# Power.net
KiCad netlist of a schematic drawn in Altium Designer
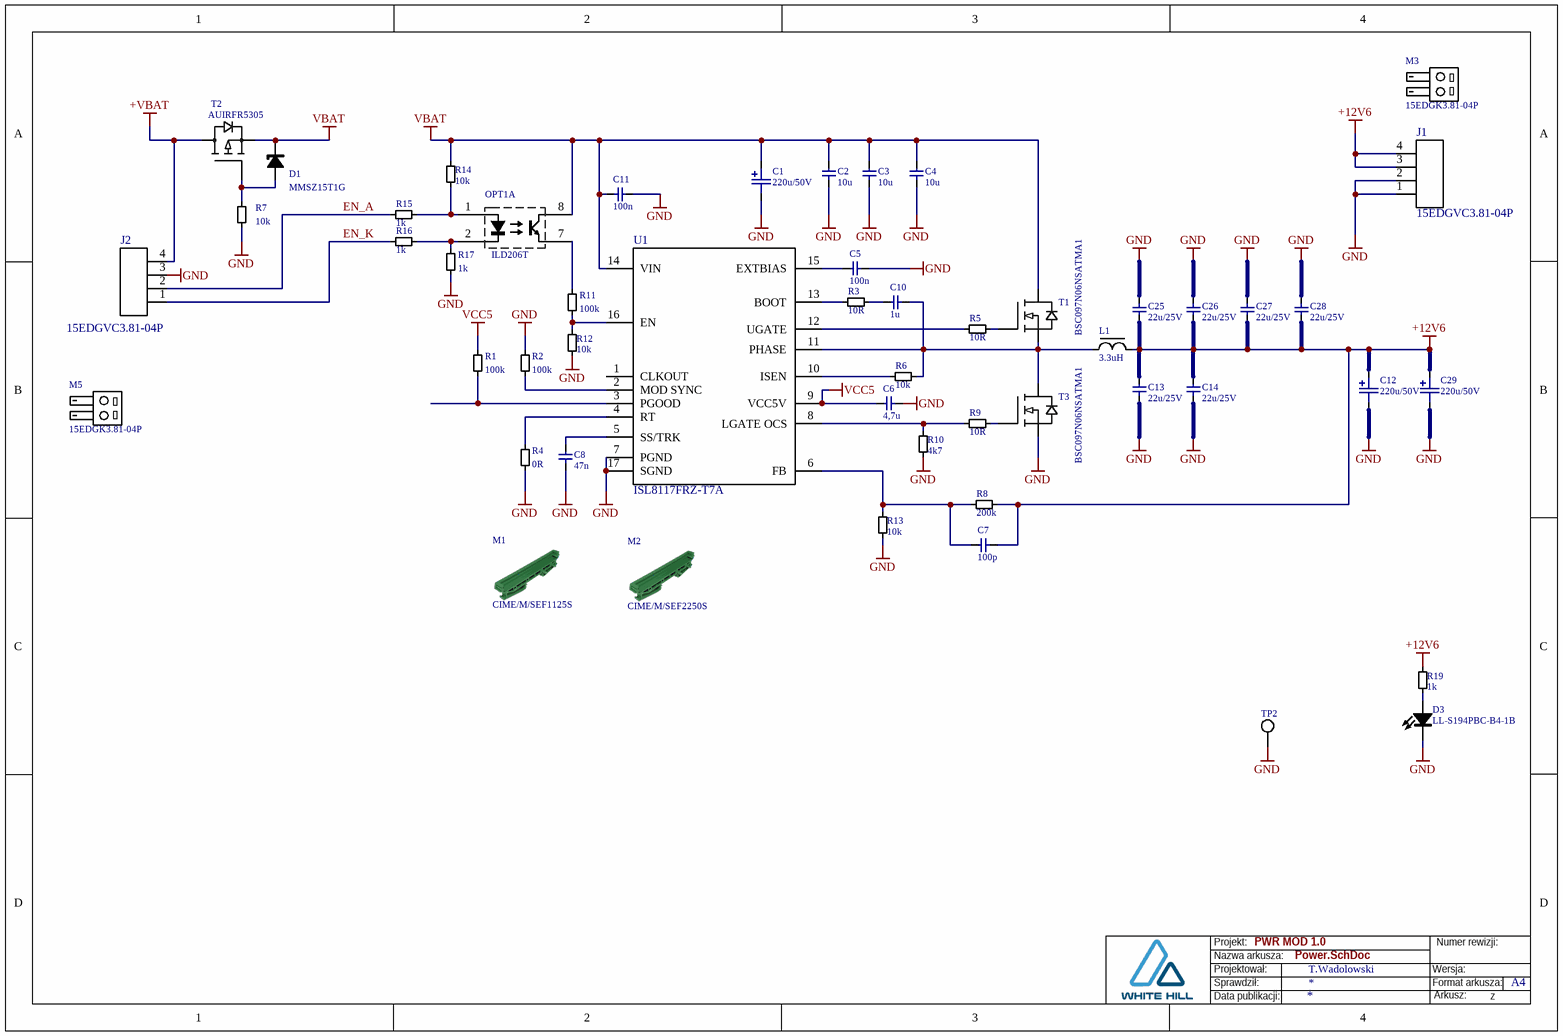
[diagram p0: Power.SchDoc]

(export (version "E")
  (design (tool "Eeschema 10.0.6"))
  (components
    (comp (ref "C1")
      (value "220u/50V")
      (footprint "ALU-G")
      (description "Capacitor: electrolytic; low impedance; 220uF; 50VDC; Case: G")
      (fields (field (name "MANUFACTURER") "Panasonic") (field (name "PART NUMBER") "EEEFP1H221AP"))
      (libsource (lib "WH") (part "CAP-EL"))
    )
    (comp (ref "C2")
      (value "10u")
      (footprint "C1206")
      (description "Capacitor: ceramic; 10uF; 50V; X7R; ±10%; SMD; 1206")
      (fields (field (name "MANUFACTURER") "Samnsung") (field (name "PART NUMBER") "CL31A106KBHNNNE"))
      (libsource (lib "CAPcer") (part "C-028"))
    )
    (comp (ref "C3")
      (value "10u")
      (footprint "C1206")
      (description "Capacitor: ceramic; 10uF; 50V; X7R; ±10%; SMD; 1206")
      (fields (field (name "MANUFACTURER") "Samnsung") (field (name "PART NUMBER") "CL31A106KBHNNNE"))
      (libsource (lib "CAPcer") (part "C-028"))
    )
    (comp (ref "C4")
      (value "10u")
      (footprint "C1206")
      (description "Capacitor: ceramic; 10uF; 50V; X7R; ±10%; SMD; 1206")
      (fields (field (name "MANUFACTURER") "Samnsung") (field (name "PART NUMBER") "CL31A106KBHNNNE"))
      (libsource (lib "CAPcer") (part "C-028"))
    )
    (comp (ref "C5")
      (value "100n")
      (footprint "C0603")
      (description "Capacitor: ceramic; 100nF; 50V; X7R; ±10%; SMD; 0603; Series: GRM")
      (fields (field (name "MANUFACTURER") "Murata") (field (name "PART NUMBER") "GRM188R71H104KA93D"))
      (libsource (lib "CAPcer") (part "C-013"))
    )
    (comp (ref "C6")
      (value "4,7u")
      (footprint "C0603")
      (description "Capacitor: ceramic;4,7uF ; 50V; X7R; ±5%; SMD; 0603")
      (fields (field (name "MANUFACTURER") "Samsung") (field (name "PART NUMBER") "0603X475K100CT"))
      (libsource (lib "CAPcer") (part "C-031"))
    )
    (comp (ref "C7")
      (value "100p")
      (footprint "C0603")
      (description "Capacitor: ceramic; MLCC; 100pF; 50V; C0G; ±1%; SMD; 0603")
      (fields (field (name "MANUFACTURER") "Vishay") (field (name "PART NUMBER") "VJ0603A101FXACW1BC"))
      (libsource (lib "CAPcer") (part "C-005"))
    )
    (comp (ref "C8")
      (value "47n")
      (footprint "C0603")
      (description "Capacitor: ceramic; MLCC; 47nF; 50V; X7R; ±10%; SMD; 0603")
      (fields (field (name "MANUFACTURER") "Kemet") (field (name "PART NUMBER") "C0603C473K5RACTU"))
      (libsource (lib "CAPcer") (part "C-012"))
    )
    (comp (ref "C10")
      (value "1u")
      (footprint "C0805-10")
      (description "Capacitor: ceramic; MLCC; 1uF; 50V; X7R; SMD; 0805")
      (fields (field (name "MANUFACTURER") "Samsung") (field (name "PART NUMBER") "CL21B105KBFNNNG"))
      (libsource (lib "CAPcer") (part "C-017"))
    )
    (comp (ref "C11")
      (value "100n")
      (footprint "C0603")
      (description "Capacitor: ceramic; 100nF; 50V; X7R; ±10%; SMD; 0603; Series: GRM")
      (fields (field (name "MANUFACTURER") "Murata") (field (name "PART NUMBER") "GRM188R71H104KA93D"))
      (libsource (lib "CAPcer") (part "C-013"))
    )
    (comp (ref "C12")
      (value "220u/50V")
      (footprint "ALU-G")
      (description "Capacitor: electrolytic; low impedance; 220uF; 50VDC; Case: G")
      (fields (field (name "MANUFACTURER") "Panasonic") (field (name "PART NUMBER") "EEEFP1H221AP"))
      (libsource (lib "WH") (part "CAP-EL"))
    )
    (comp (ref "C13")
      (value "22u/25V")
      (footprint "C1206")
      (description "Capacitor: ceramic; 22uF; 25V; X7R; ±10%; SMD; 1206")
      (fields (field (name "MANUFACTURER") "Murata") (field (name "PART NUMBER") "GRM31CR61E226KE15L"))
      (libsource (lib "CAPcer") (part "C-029"))
    )
    (comp (ref "C14")
      (value "22u/25V")
      (footprint "C1206")
      (description "Capacitor: ceramic; 22uF; 25V; X7R; ±10%; SMD; 1206")
      (fields (field (name "MANUFACTURER") "Murata") (field (name "PART NUMBER") "GRM31CR61E226KE15L"))
      (libsource (lib "CAPcer") (part "C-029"))
    )
    (comp (ref "C25")
      (value "22u/25V")
      (footprint "C1206")
      (description "Capacitor: ceramic; 22uF; 25V; X7R; ±10%; SMD; 1206")
      (fields (field (name "MANUFACTURER") "Murata") (field (name "PART NUMBER") "GRM31CR61E226KE15L"))
      (libsource (lib "CAPcer") (part "C-029"))
    )
    (comp (ref "C26")
      (value "22u/25V")
      (footprint "C1206")
      (description "Capacitor: ceramic; 22uF; 25V; X7R; ±10%; SMD; 1206")
      (fields (field (name "MANUFACTURER") "Murata") (field (name "PART NUMBER") "GRM31CR61E226KE15L"))
      (libsource (lib "CAPcer") (part "C-029"))
    )
    (comp (ref "C27")
      (value "22u/25V")
      (footprint "C1206")
      (description "Capacitor: ceramic; 22uF; 25V; X7R; ±10%; SMD; 1206")
      (fields (field (name "MANUFACTURER") "Murata") (field (name "PART NUMBER") "GRM31CR61E226KE15L"))
      (libsource (lib "CAPcer") (part "C-029"))
    )
    (comp (ref "C28")
      (value "22u/25V")
      (footprint "C1206")
      (description "Capacitor: ceramic; 22uF; 25V; X7R; ±10%; SMD; 1206")
      (fields (field (name "MANUFACTURER") "Murata") (field (name "PART NUMBER") "GRM31CR61E226KE15L"))
      (libsource (lib "CAPcer") (part "C-029"))
    )
    (comp (ref "C29")
      (value "220u/50V")
      (footprint "ALU-G")
      (description "Capacitor: electrolytic; low impedance; 220uF; 50VDC; Case: G")
      (fields (field (name "MANUFACTURER") "Panasonic") (field (name "PART NUMBER") "EEEFP1H221AP"))
      (libsource (lib "WH") (part "CAP-EL"))
    )
    (comp (ref "D1")
      (value "MMSZ15T1G")
      (footprint "SOD123")
      (description "Dioda: Zenera; 0,5W; 18V; SMD")
      (fields (field (name "MANUFACTURER") "ON Semi"))
      (libsource (lib "DGI") (part "D_ZEN"))
    )
    (comp (ref "D3")
      (value "LL-S194PBC-B4-1B")
      (footprint "LED0603B")
      (description "LED; SMD; 0603; blue; 20-40mcd; 1.6x0.8x0.4mm; 130°; 2.8÷3.8V; 20mA")
      (fields (field (name "MANUFACTURER") "LuckyLight"))
      (libsource (lib "DGI") (part "LED_1"))
    )
    (comp (ref "J1")
      (value "15EDGVC3.81-04P")
      (footprint "MCV1,5/4-G3,81")
      (description "Terminal block; 3.81mm; ways: 4; straight; socket; male")
      (fields
        (field (name "MANUFACTURER") "Degson")
        (field (name "PART NUMBER") "15EDGVC-3.81-04P-14-00A(H)")
      )
      (libsource (lib "") (part "CON4_1"))
    )
    (comp (ref "J2")
      (value "15EDGVC3.81-04P")
      (footprint "MCV1,5/4-G3,81")
      (description "Terminal block; 3.81mm; ways: 4; straight; socket; male")
      (fields
        (field (name "MANUFACTURER") "Degson")
        (field (name "PART NUMBER") "15EDGVC-3.81-04P-14-00A(H)")
      )
      (libsource (lib "WH") (part "CON4"))
    )
    (comp (ref "L1")
      (value "3.3uH")
      (footprint "HPI1260")
      (description "Inductor: wire; SMD; 3.3uH; Ioper:14A; 2.45mOhm; ±20%; Isat:15A")
      (fields (field (name "MANUFACTURER") "Ferrocore") (field (name "PART NUMBER") "HPI1260-3R3"))
      (libsource (lib "WH") (part "L_HPI_3.3uH"))
    )
    (comp (ref "M1")
      (value "CIME/M/SEF1125S")
      (description "End Section ,Foot Modular Interface Support, 72mm  11.25mm")
      (fields (field (name "MANUFACTURER") "Camdenboss"))
      (libsource (lib "WH") (part "Cime 72 11,25mm_Foot"))
    )
    (comp (ref "M2")
      (value "CIME/M/SEF2250S")
      (description "End Section ,Foot Modular Interface Support, 72mm  22,5mm")
      (fields (field (name "MANUFACTURER") "Camdenboss"))
      (libsource (lib "WH") (part "Cime 72 22,5mm_Foot"))
    )
    (comp (ref "M3")
      (value "15EDGK3.81-04P")
      (description "Pluggable terminal block; 3.81mm; ways:4; straight; plug; female")
      (fields (field (name "MANUFACTURER") "Degson") (field (name "PART NUMBER") "15EDGK-3.81-04P-14-00A(H)"))
      (libsource (lib "WH") (part "Wtyk 3,81"))
    )
    (comp (ref "M5")
      (value "15EDGK3.81-04P")
      (description "Pluggable terminal block; 3.81mm; ways:4; straight; plug; female")
      (fields (field (name "MANUFACTURER") "Degson") (field (name "PART NUMBER") "15EDGK-3.81-04P-14-00A(H)"))
      (libsource (lib "WH") (part "Wtyk 3,81"))
    )
    (comp (ref "OPT1")
      (value "ILD206T")
      (footprint "SO-8-OPT")
      (description "Transoptor; SMD; Kanały:2; Wyj: tranzystorowe; Uizol:4kV; Uce:70V")
      (fields (field (name "MANUFACTURER") "VISHAY"))
      (libsource (lib "WH") (part "Opto_dual"))
    )
    (comp (ref "R1")
      (value "100k")
      (footprint "R0603")
      (description "Resistor: thick film; SMD; 0603; 100k; 0.125W; ±5%")
      (fields (field (name "MANUFACTURER") "Walsin") (field (name "PART NUMBER") "WF06P104JTL"))
      (libsource (lib "Resistors") (part "R-013"))
    )
    (comp (ref "R2")
      (value "100k")
      (footprint "R0603")
      (description "Resistor: thick film; SMD; 0603; 100k; 0.125W; ±5%")
      (fields (field (name "MANUFACTURER") "Walsin") (field (name "PART NUMBER") "WF06P104JTL"))
      (libsource (lib "Resistors") (part "R-013"))
    )
    (comp (ref "R3")
      (value "10R")
      (footprint "R0603")
      (description "Resistor: thick film; SMD; 0603; 10R; 0.1W; ±5%")
      (fields (field (name "MANUFACTURER") "Royal Ohm") (field (name "PART NUMBER") "0603SAJ0100T5E"))
      (libsource (lib "Resistors") (part "R-001"))
    )
    (comp (ref "R4")
      (value "0R")
      (footprint "R0603")
      (description "Resistor: thick film; SMD; 0603; 0R; 0.125W; ±5%")
      (fields (field (name "MANUFACTURER") "Royal Ohm") (field (name "PART NUMBER") "CRCW06030000Z0TABC"))
      (libsource (lib "Resistors") (part "R-018"))
    )
    (comp (ref "R5")
      (value "10R")
      (footprint "R0603")
      (description "Resistor: thick film; SMD; 0603; 10R; 0.1W; ±5%")
      (fields (field (name "MANUFACTURER") "Royal Ohm") (field (name "PART NUMBER") "0603SAJ0100T5E"))
      (libsource (lib "Resistors") (part "R-001"))
    )
    (comp (ref "R6")
      (value "10k")
      (footprint "R0603")
      (description "Resistor: thick film; SMD; 0603; 10k; 0.125W; ±5%")
      (fields (field (name "MANUFACTURER") "Walsin") (field (name "PART NUMBER") "WF06P103JTL"))
      (libsource (lib "Resistors") (part "R-012"))
    )
    (comp (ref "R7")
      (value "10k")
      (footprint "R0603")
      (description "Resistor: thick film; SMD; 0603; 10k; 0.125W; ±5%")
      (fields (field (name "MANUFACTURER") "Walsin") (field (name "PART NUMBER") "WF06P103JTL"))
      (libsource (lib "") (part "R-012_1"))
    )
    (comp (ref "R8")
      (value "200k")
      (footprint "R0603")
      (description "Resistor: thick film; SMD; 0805; 200k; 0.125W; ±5%;")
      (fields (field (name "MANUFACTURER") "Royal Ohm") (field (name "PART NUMBER") "0603SAJ0204T5E"))
      (libsource (lib "Resistors") (part "R-042"))
    )
    (comp (ref "R9")
      (value "10R")
      (footprint "R0603")
      (description "Resistor: thick film; SMD; 0603; 10R; 0.1W; ±5%")
      (fields (field (name "MANUFACTURER") "Royal Ohm") (field (name "PART NUMBER") "0603SAJ0100T5E"))
      (libsource (lib "Resistors") (part "R-001"))
    )
    (comp (ref "R10")
      (value "4k7")
      (footprint "R0603")
      (description "Resistor: thick film; SMD; 0603; 4.7k; 0.125W; ±5%")
      (fields (field (name "MANUFACTURER") "Walsin") (field (name "PART NUMBER") "WF06P472JTL"))
      (libsource (lib "Resistors") (part "R-011"))
    )
    (comp (ref "R11")
      (value "100k")
      (footprint "R0603")
      (description "Resistor: thick film; SMD; 0603; 100k; 0.125W; ±5%")
      (fields (field (name "MANUFACTURER") "Walsin") (field (name "PART NUMBER") "WF06P104JTL"))
      (libsource (lib "Resistors") (part "R-013"))
    )
    (comp (ref "R12")
      (value "10k")
      (footprint "R0603")
      (description "Resistor: thick film; SMD; 0603; 10k; 0.125W; ±5%")
      (fields (field (name "MANUFACTURER") "Walsin") (field (name "PART NUMBER") "WF06P103JTL"))
      (libsource (lib "") (part "R-012_1"))
    )
    (comp (ref "R13")
      (value "10k")
      (footprint "R0603")
      (description "Resistor: thick film; SMD; 0603; 10k; 0.125W; ±5%")
      (fields (field (name "MANUFACTURER") "Walsin") (field (name "PART NUMBER") "WF06P103JTL"))
      (libsource (lib "") (part "R-012_1"))
    )
    (comp (ref "R14")
      (value "10k")
      (footprint "R0603")
      (description "Resistor: thick film; SMD; 0603; 10k; 0.125W; ±5%")
      (fields (field (name "MANUFACTURER") "Walsin") (field (name "PART NUMBER") "WF06P103JTL"))
      (libsource (lib "") (part "R-012_1"))
    )
    (comp (ref "R15")
      (value "1k")
      (footprint "R0603")
      (description "Resistor: thick film; SMD; 0603; 1k; 0.1W; ±5%")
      (fields (field (name "MANUFACTURER") "Royal Ohm") (field (name "PART NUMBER") "0603SAJ0102T5E"))
      (libsource (lib "") (part "R-005_2"))
    )
    (comp (ref "R16")
      (value "1k")
      (footprint "R0603")
      (description "Resistor: thick film; SMD; 0603; 1k; 0.1W; ±5%")
      (fields (field (name "MANUFACTURER") "Royal Ohm") (field (name "PART NUMBER") "0603SAJ0102T5E"))
      (libsource (lib "") (part "R-005_2"))
    )
    (comp (ref "R17")
      (value "1k")
      (footprint "R0603")
      (description "Resistor: thick film; SMD; 0603; 1k; 0.1W; ±5%")
      (fields (field (name "MANUFACTURER") "Royal Ohm") (field (name "PART NUMBER") "0603SAJ0102T5E"))
      (libsource (lib "") (part "R-005_1"))
    )
    (comp (ref "R19")
      (value "1k")
      (footprint "R0603")
      (description "Resistor: thick film; SMD; 0603; 1k; 0.1W; ±5%")
      (fields (field (name "MANUFACTURER") "Royal Ohm") (field (name "PART NUMBER") "0603SAJ0102T5E"))
      (libsource (lib "Resistors") (part "R-005"))
    )
    (comp (ref "T1")
      (value "BSC097N06NSATMA1")
      (footprint "PowerPAK SO-8")
      (description "Transistor N MOS 60V;10 mOhm;46A")
      (fields (field (name "MANUFACTURER") "Infineon"))
      (libsource (lib "WH") (part "NVMFS5C426NAFT1G"))
    )
    (comp (ref "T2")
      (value "AUIRFR5305")
      (footprint "DPAK")
      (description "Transistor: P-MOSFET; unipolar; -55V; -31A; 110W; DPAK")
      (fields (field (name "MANUFACTURER") "IR"))
      (libsource (lib "DGI") (part "IRFR5410PBF"))
    )
    (comp (ref "T3")
      (value "BSC097N06NSATMA1")
      (footprint "PowerPAK SO-8")
      (description "Transistor N MOS 60V;10 mOhm;46A")
      (fields (field (name "MANUFACTURER") "Infineon"))
      (libsource (lib "WH") (part "NVMFS5C426NAFT1G"))
    )
    (comp (ref "TP2")
      (value "TEST-1R")
      (footprint "TP-O")
      (description "Sprezynka pomiarowa czerwona")
      (libsource (lib "WH") (part "TP_O"))
    )
    (comp (ref "U1")
      (value "ISL8117FRZ-T7A")
      (footprint "QFN-16-0.5")
      (description "Synchronous Step-Down PWM Controller 60V 2MHz")
      (fields (field (name "MANUFACTURER") "Renesas"))
      (libsource (lib "WH") (part "ISL8117"))
    )
  )
  (nets
    (net (code "1") (name "+12V6") (class "Default")
      (node (ref "C12") (pin "1") (pinfunction "1_1") (pintype "passive"))
      (node (ref "C13") (pin "1") (pinfunction "1_1") (pintype "passive"))
      (node (ref "C14") (pin "1") (pinfunction "1_1") (pintype "passive"))
      (node (ref "C25") (pin "1") (pinfunction "1_1") (pintype "passive"))
      (node (ref "C26") (pin "1") (pinfunction "1_1") (pintype "passive"))
      (node (ref "C27") (pin "1") (pinfunction "1_1") (pintype "passive"))
      (node (ref "C28") (pin "1") (pinfunction "1_1") (pintype "passive"))
      (node (ref "C29") (pin "1") (pinfunction "1_1") (pintype "passive"))
      (node (ref "C7") (pin "2") (pinfunction "2_2") (pintype "passive"))
      (node (ref "J1") (pin "3") (pinfunction "3_3") (pintype "passive"))
      (node (ref "J1") (pin "4") (pinfunction "4_4") (pintype "passive"))
      (node (ref "L1") (pin "2") (pinfunction "2_2") (pintype "passive"))
      (node (ref "R19") (pin "1") (pinfunction "TOP_1") (pintype "passive"))
      (node (ref "R8") (pin "1") (pinfunction "TOP_1") (pintype "passive"))
    )
    (net (code "2") (name "+VBAT") (class "Default")
      (node (ref "J2") (pin "4") (pinfunction "4_4") (pintype "passive"))
      (node (ref "T2") (pin "2") (pinfunction "D_2") (pintype "passive"))
    )
    (net (code "3") (name "/EN_A") (class "Default")
      (node (ref "J2") (pin "2") (pinfunction "2_2") (pintype "passive"))
      (node (ref "R15") (pin "1") (pinfunction "TOP_1") (pintype "passive"))
    )
    (net (code "4") (name "/EN_K") (class "Default")
      (node (ref "J2") (pin "1") (pinfunction "1_1") (pintype "passive"))
      (node (ref "R16") (pin "1") (pinfunction "TOP_1") (pintype "passive"))
    )
    (net (code "5") (name "GND") (class "Default")
      (node (ref "C1") (pin "2") (pinfunction "2_2") (pintype "passive"))
      (node (ref "C11") (pin "1") (pinfunction "1_1") (pintype "passive"))
      (node (ref "C12") (pin "2") (pinfunction "2_2") (pintype "passive"))
      (node (ref "C13") (pin "2") (pinfunction "2_2") (pintype "passive"))
      (node (ref "C14") (pin "2") (pinfunction "2_2") (pintype "passive"))
      (node (ref "C2") (pin "2") (pinfunction "2_2") (pintype "passive"))
      (node (ref "C25") (pin "2") (pinfunction "2_2") (pintype "passive"))
      (node (ref "C26") (pin "2") (pinfunction "2_2") (pintype "passive"))
      (node (ref "C27") (pin "2") (pinfunction "2_2") (pintype "passive"))
      (node (ref "C28") (pin "2") (pinfunction "2_2") (pintype "passive"))
      (node (ref "C29") (pin "2") (pinfunction "2_2") (pintype "passive"))
      (node (ref "C3") (pin "2") (pinfunction "2_2") (pintype "passive"))
      (node (ref "C4") (pin "2") (pinfunction "2_2") (pintype "passive"))
      (node (ref "C5") (pin "2") (pinfunction "2_2") (pintype "passive"))
      (node (ref "C6") (pin "2") (pinfunction "2_2") (pintype "passive"))
      (node (ref "C8") (pin "2") (pinfunction "2_2") (pintype "passive"))
      (node (ref "D3") (pin "K") (pinfunction "K_K") (pintype "passive"))
      (node (ref "J1") (pin "1") (pinfunction "1_1") (pintype "passive"))
      (node (ref "J1") (pin "2") (pinfunction "2_2") (pintype "passive"))
      (node (ref "J2") (pin "3") (pinfunction "3_3") (pintype "passive"))
      (node (ref "R10") (pin "1") (pinfunction "TOP_1") (pintype "passive"))
      (node (ref "R12") (pin "2") (pinfunction "BOT_2") (pintype "passive"))
      (node (ref "R13") (pin "2") (pinfunction "BOT_2") (pintype "passive"))
      (node (ref "R17") (pin "1") (pinfunction "TOP_1") (pintype "passive"))
      (node (ref "R2") (pin "2") (pinfunction "BOT_2") (pintype "passive"))
      (node (ref "R4") (pin "2") (pinfunction "BOT_2") (pintype "passive"))
      (node (ref "R7") (pin "2") (pinfunction "BOT_2") (pintype "passive"))
      (node (ref "T3") (pin "S") (pinfunction "S_S") (pintype "passive"))
      (node (ref "TP2") (pin "1") (pinfunction "1_1") (pintype "passive"))
      (node (ref "U1") (pin "17") (pinfunction "SGND_17") (pintype "passive"))
      (node (ref "U1") (pin "7") (pinfunction "PGND_7") (pintype "passive"))
    )
    (net (code "6") (name "Net-(D1-A)") (class "Default")
      (node (ref "D1") (pin "1") (pinfunction "A_1") (pintype "passive"))
      (node (ref "R7") (pin "1") (pinfunction "TOP_1") (pintype "passive"))
      (node (ref "T2") (pin "1") (pinfunction "G_1") (pintype "passive"))
    )
    (net (code "7") (name "Net-(R1-TOP)") (class "Default")
      (node (ref "R1") (pin "1") (pinfunction "TOP_1") (pintype "passive"))
      (node (ref "U1") (pin "3") (pinfunction "PGOOD_3") (pintype "passive"))
    )
    (net (code "8") (name "Net-(R2-TOP)") (class "Default")
      (node (ref "R2") (pin "1") (pinfunction "TOP_1") (pintype "passive"))
      (node (ref "U1") (pin "2") (pinfunction "MOD_SYNC_2") (pintype "passive"))
    )
    (net (code "9") (name "Net-(R3-BOT)") (class "Default")
      (node (ref "R3") (pin "2") (pinfunction "BOT_2") (pintype "passive"))
      (node (ref "U1") (pin "13") (pinfunction "BOOT_13") (pintype "passive"))
    )
    (net (code "10") (name "Net-(R3-TOP)") (class "Default")
      (node (ref "C10") (pin "1") (pinfunction "1_1") (pintype "passive"))
      (node (ref "R3") (pin "1") (pinfunction "TOP_1") (pintype "passive"))
    )
    (net (code "11") (name "Net-(R4-TOP)") (class "Default")
      (node (ref "R4") (pin "1") (pinfunction "TOP_1") (pintype "passive"))
      (node (ref "U1") (pin "4") (pinfunction "RT_4") (pintype "passive"))
    )
    (net (code "12") (name "Net-(R5-BOT)") (class "Default")
      (node (ref "R5") (pin "2") (pinfunction "BOT_2") (pintype "passive"))
      (node (ref "U1") (pin "12") (pinfunction "UGATE_12") (pintype "passive"))
    )
    (net (code "13") (name "Net-(R5-TOP)") (class "Default")
      (node (ref "R5") (pin "1") (pinfunction "TOP_1") (pintype "passive"))
      (node (ref "T1") (pin "G") (pinfunction "G_G") (pintype "passive"))
    )
    (net (code "14") (name "Net-(R6-BOT)") (class "Default")
      (node (ref "R6") (pin "2") (pinfunction "BOT_2") (pintype "passive"))
      (node (ref "U1") (pin "10") (pinfunction "ISEN_10") (pintype "passive"))
    )
    (net (code "15") (name "Net-(R6-TOP)") (class "Default")
      (node (ref "C10") (pin "2") (pinfunction "2_2") (pintype "passive"))
      (node (ref "L1") (pin "1") (pinfunction "1_1") (pintype "passive"))
      (node (ref "R6") (pin "1") (pinfunction "TOP_1") (pintype "passive"))
      (node (ref "T1") (pin "S") (pinfunction "S_S") (pintype "passive"))
      (node (ref "T3") (pin "D") (pinfunction "D_D") (pintype "passive"))
      (node (ref "U1") (pin "11") (pinfunction "PHASE_11") (pintype "passive"))
    )
    (net (code "16") (name "Net-(R9-TOP)") (class "Default")
      (node (ref "R9") (pin "1") (pinfunction "TOP_1") (pintype "passive"))
      (node (ref "T3") (pin "G") (pinfunction "G_G") (pintype "passive"))
    )
    (net (code "17") (name "Net-(R10-BOT)") (class "Default")
      (node (ref "R10") (pin "2") (pinfunction "BOT_2") (pintype "passive"))
      (node (ref "R9") (pin "2") (pinfunction "BOT_2") (pintype "passive"))
      (node (ref "U1") (pin "8") (pinfunction "LGATE_OCS_8") (pintype "passive"))
    )
    (net (code "18") (name "Net-(R11-BOT)") (class "Default")
      (node (ref "OPT1") (pin "7") (pinfunction "7_7") (pintype "passive"))
      (node (ref "R11") (pin "2") (pinfunction "BOT_2") (pintype "passive"))
    )
    (net (code "19") (name "Net-(R11-TOP)") (class "Default")
      (node (ref "R11") (pin "1") (pinfunction "TOP_1") (pintype "passive"))
      (node (ref "R12") (pin "1") (pinfunction "TOP_1") (pintype "passive"))
      (node (ref "U1") (pin "16") (pinfunction "EN_16") (pintype "passive"))
    )
    (net (code "20") (name "Net-(R13-TOP)") (class "Default")
      (node (ref "C7") (pin "1") (pinfunction "1_1") (pintype "passive"))
      (node (ref "R13") (pin "1") (pinfunction "TOP_1") (pintype "passive"))
      (node (ref "R8") (pin "2") (pinfunction "BOT_2") (pintype "passive"))
      (node (ref "U1") (pin "6") (pinfunction "FB_6") (pintype "passive"))
    )
    (net (code "21") (name "Net-(R14-BOT)") (class "Default")
      (node (ref "OPT1") (pin "1") (pinfunction "1_1") (pintype "passive"))
      (node (ref "R14") (pin "2") (pinfunction "BOT_2") (pintype "passive"))
      (node (ref "R15") (pin "2") (pinfunction "BOT_2") (pintype "passive"))
    )
    (net (code "22") (name "Net-(R16-BOT)") (class "Default")
      (node (ref "OPT1") (pin "2") (pinfunction "2_2") (pintype "passive"))
      (node (ref "R16") (pin "2") (pinfunction "BOT_2") (pintype "passive"))
      (node (ref "R17") (pin "2") (pinfunction "BOT_2") (pintype "passive"))
    )
    (net (code "23") (name "Net-(R19-BOT)") (class "Default")
      (node (ref "D3") (pin "A") (pinfunction "A_A") (pintype "passive"))
      (node (ref "R19") (pin "2") (pinfunction "BOT_2") (pintype "passive"))
    )
    (net (code "24") (name "Net-(U1-EXTBIAS)") (class "Default")
      (node (ref "C5") (pin "1") (pinfunction "1_1") (pintype "passive"))
      (node (ref "U1") (pin "15") (pinfunction "EXTBIAS_15") (pintype "power_in"))
    )
    (net (code "25") (name "Net-(U1-SS{slash}TRK)") (class "Default")
      (node (ref "C8") (pin "1") (pinfunction "1_1") (pintype "passive"))
      (node (ref "U1") (pin "5") (pinfunction "SS/TRK_5") (pintype "passive"))
    )
    (net (code "26") (name "VBAT") (class "Default")
      (node (ref "C1") (pin "1") (pinfunction "1_1") (pintype "passive"))
      (node (ref "C11") (pin "2") (pinfunction "2_2") (pintype "passive"))
      (node (ref "C2") (pin "1") (pinfunction "1_1") (pintype "passive"))
      (node (ref "C3") (pin "1") (pinfunction "1_1") (pintype "passive"))
      (node (ref "C4") (pin "1") (pinfunction "1_1") (pintype "passive"))
      (node (ref "D1") (pin "2") (pinfunction "K_2") (pintype "passive"))
      (node (ref "OPT1") (pin "8") (pinfunction "8_8") (pintype "passive"))
      (node (ref "R14") (pin "1") (pinfunction "TOP_1") (pintype "passive"))
      (node (ref "T1") (pin "D") (pinfunction "D_D") (pintype "passive"))
      (node (ref "T2") (pin "3") (pinfunction "S_3") (pintype "passive"))
      (node (ref "U1") (pin "14") (pinfunction "VIN_14") (pintype "passive"))
    )
    (net (code "27") (name "VCC5") (class "Default")
      (node (ref "C6") (pin "1") (pinfunction "1_1") (pintype "passive"))
      (node (ref "R1") (pin "2") (pinfunction "BOT_2") (pintype "passive"))
      (node (ref "U1") (pin "9") (pinfunction "VCC5V_9") (pintype "passive"))
    )
    (net (code "28") (name "unconnected-(U1-CLKOUT-Pad1)") (class "Default")
      (node (ref "U1") (pin "1") (pinfunction "CLKOUT_1") (pintype "passive"))
    )
  )
)
